# 02_BLBB_MCU.net
KiCad netlist of a schematic drawn in Altium Designer
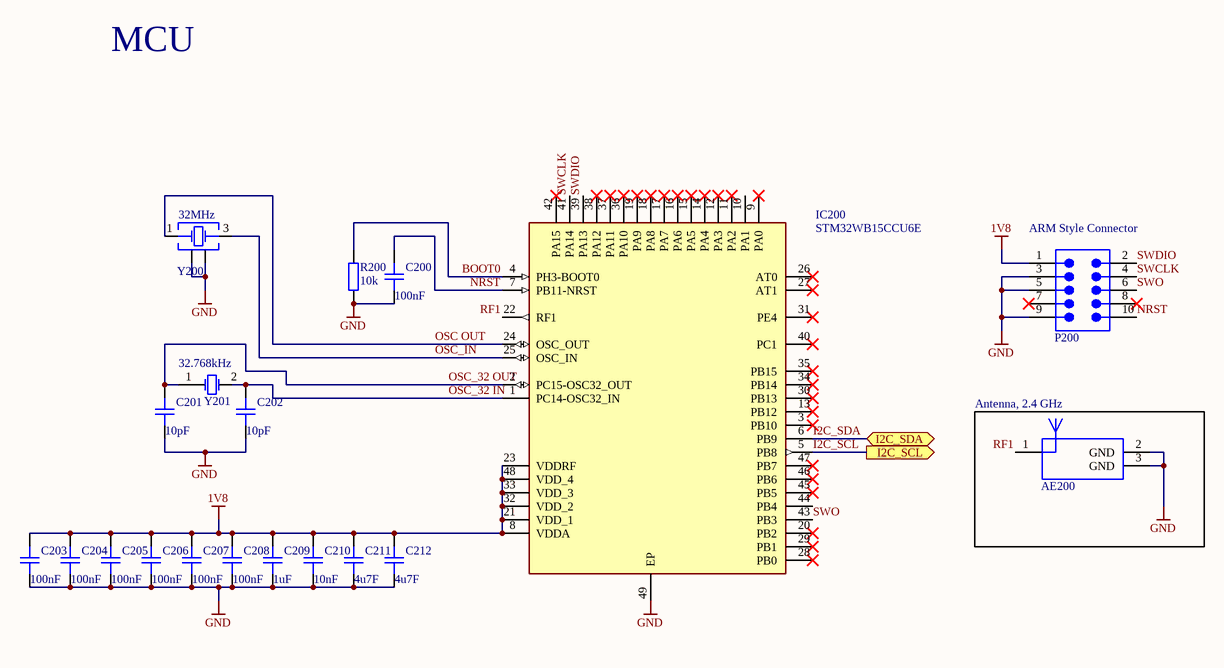
[diagram p0: 02_BLBB_MCU.SchDoc]

(export (version "E")
  (design (tool "Eeschema 10.0.6"))
  (components
    (comp (ref "AE200")
      (value "7488960245")
      (footprint "7488960245")
      (description "WE-MCA SMT Multilayer Chip Antenna, 1 Band, 2400-2500MHz, 50Ω")
      (fields (field (name "MANUFACTURER") "Wurth Elektronik"))
      (libsource (lib "WE-MCA") (part "7488960245"))
    )
    (comp (ref "C200")
      (value "100nF")
      (footprint "CAP_0603")
      (description "Capacitor SMD 0603 10V")
      (libsource (lib "Schematic-Lib-PhilsLab") (part "CAP_0603_10V"))
    )
    (comp (ref "C201")
      (value "10pF")
      (footprint "CAP_0603")
      (description "Capacitor SMD 0603 10V")
      (libsource (lib "Schematic-Lib-PhilsLab") (part "CAP_0603_10V"))
    )
    (comp (ref "C202")
      (value "10pF")
      (footprint "CAP_0603")
      (description "Capacitor SMD 0603 10V")
      (libsource (lib "Schematic-Lib-PhilsLab") (part "CAP_0603_10V"))
    )
    (comp (ref "C203")
      (value "100nF")
      (footprint "CAP_0603")
      (description "Capacitor SMD 0603 10V")
      (libsource (lib "Schematic-Lib-PhilsLab") (part "CAP_0603_10V"))
    )
    (comp (ref "C204")
      (value "100nF")
      (footprint "CAP_0603")
      (description "Capacitor SMD 0603 10V")
      (libsource (lib "Schematic-Lib-PhilsLab") (part "CAP_0603_10V"))
    )
    (comp (ref "C205")
      (value "100nF")
      (footprint "CAP_0603")
      (description "Capacitor SMD 0603 10V")
      (libsource (lib "Schematic-Lib-PhilsLab") (part "CAP_0603_10V"))
    )
    (comp (ref "C206")
      (value "100nF")
      (footprint "CAP_0603")
      (description "Capacitor SMD 0603 10V")
      (libsource (lib "Schematic-Lib-PhilsLab") (part "CAP_0603_10V"))
    )
    (comp (ref "C207")
      (value "100nF")
      (footprint "CAP_0603")
      (description "Capacitor SMD 0603 10V")
      (libsource (lib "Schematic-Lib-PhilsLab") (part "CAP_0603_10V"))
    )
    (comp (ref "C208")
      (value "100nF")
      (footprint "CAP_0603")
      (description "Capacitor SMD 0603 10V")
      (libsource (lib "Schematic-Lib-PhilsLab") (part "CAP_0603_10V"))
    )
    (comp (ref "C209")
      (value "1uF")
      (footprint "CAP_0603")
      (description "Capacitor SMD 0603 10V")
      (libsource (lib "Schematic-Lib-PhilsLab") (part "CAP_0603_10V"))
    )
    (comp (ref "C210")
      (value "10nF")
      (footprint "CAP_0603")
      (description "Capacitor SMD 0603 10V")
      (libsource (lib "Schematic-Lib-PhilsLab") (part "CAP_0603_10V"))
    )
    (comp (ref "C211")
      (value "4u7F")
      (footprint "CAP_0603")
      (description "Capacitor SMD 0603 10V")
      (libsource (lib "Schematic-Lib-PhilsLab") (part "CAP_0603_10V"))
    )
    (comp (ref "C212")
      (value "4u7F")
      (footprint "CAP_0603")
      (description "Capacitor SMD 0603 10V")
      (libsource (lib "Schematic-Lib-PhilsLab") (part "CAP_0603_10V"))
    )
    (comp (ref "IC200")
      (value "STM32WB15CCU6E")
      (footprint "SamacSys:QFN50P700X700X65-49N-D")
      (description "Integrated Circuit")
      (fields (field (name "MOUSER PART NUMBER") "511-STM32WB15CCU6E"))
      (libsource (lib "SamacSys") (part "STM32WB15CCU6E"))
    )
    (comp (ref "P200")
      (value "62701020621")
      (footprint "62701020621")
      (description "WR-BHD Male Box Header, SMT Straight, pitch 1.27mm, 10pins")
      (fields (field (name "MANUFACTURER") "Wurth Elektronik"))
      (libsource (lib "Altium_WR-BHD (rev22b)") (part "62701020621"))
    )
    (comp (ref "R200")
      (value "10k")
      (footprint "RES_0603")
      (description "Resistor SMD 0603")
      (libsource (lib "Schematic-Lib-PhilsLab") (part "RES_0603"))
    )
    (comp (ref "Y200")
      (value "32MHz")
      (footprint "WE-XTAL_CFPX-180")
      (description "WE-XTAL Quartz Crystal, SMT, CFPX-180, 32MHz, +/-30ppm")
      (fields
        (field (name "MANUFACTURER PART NUMBER") "830060258")
        (field (name "MANUFACTURER") "Wurth Elektronik")
      )
      (libsource (lib "WE-XTAL") (part "830060258"))
    )
    (comp (ref "Y201")
      (value "32.768kHz")
      (footprint "WE-XTAL_CFPX-217")
      (description "WE-XTAL Watch Crystal, SMT, CFPX-217, 32.768kHz, +/-20ppm")
      (fields
        (field (name "MANUFACTURER PART NUMBER") "830009709")
        (field (name "MANUFACTURER") "Wurth Elektronik")
      )
      (libsource (lib "WE-XTAL") (part "830009709"))
    )
  )
  (nets
    (net (code "1") (name "/BOOT0") (class "Default")
      (node (ref "IC200") (pin "4") (pinfunction "PH3-BOOT0_4") (pintype "input"))
      (node (ref "R200") (pin "2") (pinfunction "2_2") (pintype "passive"))
    )
    (net (code "2") (name "/I2C_SCL") (class "Default")
      (node (ref "IC200") (pin "5") (pinfunction "PB8_5") (pintype "output"))
    )
    (net (code "3") (name "/I2C_SDA") (class "Default")
      (node (ref "IC200") (pin "6") (pinfunction "PB9_6") (pintype "passive"))
    )
    (net (code "4") (name "/NRST") (class "Default")
      (node (ref "C200") (pin "2") (pinfunction "2_2") (pintype "passive"))
      (node (ref "IC200") (pin "7") (pinfunction "PB11-NRST_7") (pintype "input"))
      (node (ref "P200") (pin "10") (pinfunction "10_10") (pintype "passive"))
    )
    (net (code "5") (name "/OSC OUT") (class "Default")
      (node (ref "IC200") (pin "24") (pinfunction "OSC_OUT_24") (pintype "bidirectional"))
      (node (ref "Y200") (pin "1") (pinfunction "Crystal_1") (pintype "passive"))
    )
    (net (code "6") (name "/OSC_32 IN") (class "Default")
      (node (ref "C202") (pin "2") (pinfunction "2_2") (pintype "passive"))
      (node (ref "IC200") (pin "1") (pinfunction "PC14-OSC32_IN_1") (pintype "open_collector"))
      (node (ref "Y201") (pin "2") (pinfunction "OSC2_2") (pintype "passive"))
    )
    (net (code "7") (name "/OSC_32 OUT") (class "Default")
      (node (ref "C201") (pin "2") (pinfunction "2_2") (pintype "passive"))
      (node (ref "IC200") (pin "2") (pinfunction "PC15-OSC32_OUT_2") (pintype "bidirectional"))
      (node (ref "Y201") (pin "1") (pinfunction "OSC1_1") (pintype "passive"))
    )
    (net (code "8") (name "/OSC_IN") (class "Default")
      (node (ref "IC200") (pin "25") (pinfunction "OSC_IN_25") (pintype "bidirectional"))
      (node (ref "Y200") (pin "3") (pinfunction "Crystal_3") (pintype "passive"))
    )
    (net (code "9") (name "/RF1") (class "Default")
      (node (ref "AE200") (pin "1") (pinfunction "Feed_1") (pintype "passive"))
      (node (ref "IC200") (pin "22") (pinfunction "RF1_22") (pintype "output"))
    )
    (net (code "10") (name "/SWCLK") (class "Default")
      (node (ref "IC200") (pin "41") (pinfunction "PA14_41") (pintype "passive"))
      (node (ref "P200") (pin "4") (pinfunction "4_4") (pintype "passive"))
    )
    (net (code "11") (name "/SWDIO") (class "Default")
      (node (ref "IC200") (pin "39") (pinfunction "PA13_39") (pintype "passive"))
      (node (ref "P200") (pin "2") (pinfunction "2_2") (pintype "passive"))
    )
    (net (code "12") (name "/SWO") (class "Default")
      (node (ref "IC200") (pin "43") (pinfunction "PB3_43") (pintype "passive"))
      (node (ref "P200") (pin "6") (pinfunction "6_6") (pintype "passive"))
    )
    (net (code "13") (name "1V8") (class "Default")
      (node (ref "C203") (pin "2") (pinfunction "2_2") (pintype "passive"))
      (node (ref "C204") (pin "2") (pinfunction "2_2") (pintype "passive"))
      (node (ref "C205") (pin "2") (pinfunction "2_2") (pintype "passive"))
      (node (ref "C206") (pin "2") (pinfunction "2_2") (pintype "passive"))
      (node (ref "C207") (pin "2") (pinfunction "2_2") (pintype "passive"))
      (node (ref "C208") (pin "2") (pinfunction "2_2") (pintype "passive"))
      (node (ref "C209") (pin "2") (pinfunction "2_2") (pintype "passive"))
      (node (ref "C210") (pin "2") (pinfunction "2_2") (pintype "passive"))
      (node (ref "C211") (pin "2") (pinfunction "2_2") (pintype "passive"))
      (node (ref "C212") (pin "2") (pinfunction "2_2") (pintype "passive"))
      (node (ref "IC200") (pin "21") (pinfunction "VDD_1_21") (pintype "passive"))
      (node (ref "IC200") (pin "23") (pinfunction "VDDRF_23") (pintype "power_in"))
      (node (ref "IC200") (pin "32") (pinfunction "VDD_2_32") (pintype "power_in"))
      (node (ref "IC200") (pin "33") (pinfunction "VDD_3_33") (pintype "power_in"))
      (node (ref "IC200") (pin "48") (pinfunction "VDD_4_48") (pintype "power_in"))
      (node (ref "IC200") (pin "8") (pinfunction "VDDA_8") (pintype "power_in"))
      (node (ref "P200") (pin "1") (pinfunction "1_1") (pintype "passive"))
    )
    (net (code "14") (name "GND") (class "Default")
      (node (ref "AE200") (pin "2") (pinfunction "GND_2") (pintype "passive"))
      (node (ref "AE200") (pin "3") (pinfunction "GND_3") (pintype "passive"))
      (node (ref "C200") (pin "1") (pinfunction "1_1") (pintype "passive"))
      (node (ref "C201") (pin "1") (pinfunction "1_1") (pintype "passive"))
      (node (ref "C202") (pin "1") (pinfunction "1_1") (pintype "passive"))
      (node (ref "C203") (pin "1") (pinfunction "1_1") (pintype "passive"))
      (node (ref "C204") (pin "1") (pinfunction "1_1") (pintype "passive"))
      (node (ref "C205") (pin "1") (pinfunction "1_1") (pintype "passive"))
      (node (ref "C206") (pin "1") (pinfunction "1_1") (pintype "passive"))
      (node (ref "C207") (pin "1") (pinfunction "1_1") (pintype "passive"))
      (node (ref "C208") (pin "1") (pinfunction "1_1") (pintype "passive"))
      (node (ref "C209") (pin "1") (pinfunction "1_1") (pintype "passive"))
      (node (ref "C210") (pin "1") (pinfunction "1_1") (pintype "passive"))
      (node (ref "C211") (pin "1") (pinfunction "1_1") (pintype "passive"))
      (node (ref "C212") (pin "1") (pinfunction "1_1") (pintype "passive"))
      (node (ref "IC200") (pin "49") (pinfunction "EP_49") (pintype "power_in"))
      (node (ref "P200") (pin "3") (pinfunction "3_3") (pintype "passive"))
      (node (ref "P200") (pin "5") (pinfunction "5_5") (pintype "passive"))
      (node (ref "P200") (pin "9") (pinfunction "9_9") (pintype "passive"))
      (node (ref "R200") (pin "1") (pinfunction "1_1") (pintype "passive"))
      (node (ref "Y200") (pin "2") (pinfunction "GND&Lid_2") (pintype "passive"))
      (node (ref "Y200") (pin "4") (pinfunction "GND&Lid_4") (pintype "passive"))
    )
    (net (code "15") (name "unconnected-(IC200-AT0-Pad26)") (class "Default")
      (node (ref "IC200") (pin "26") (pinfunction "AT0_26") (pintype "passive+no_connect"))
    )
    (net (code "16") (name "unconnected-(IC200-AT1-Pad27)") (class "Default")
      (node (ref "IC200") (pin "27") (pinfunction "AT1_27") (pintype "passive+no_connect"))
    )
    (net (code "17") (name "unconnected-(IC200-PA0-Pad9)") (class "Default")
      (node (ref "IC200") (pin "9") (pinfunction "PA0_9") (pintype "passive+no_connect"))
    )
    (net (code "18") (name "unconnected-(IC200-PA1-Pad10)") (class "Default")
      (node (ref "IC200") (pin "10") (pinfunction "PA1_10") (pintype "passive"))
    )
    (net (code "19") (name "unconnected-(IC200-PA2-Pad11)") (class "Default")
      (node (ref "IC200") (pin "11") (pinfunction "PA2_11") (pintype "passive+no_connect"))
    )
    (net (code "20") (name "unconnected-(IC200-PA3-Pad12)") (class "Default")
      (node (ref "IC200") (pin "12") (pinfunction "PA3_12") (pintype "passive+no_connect"))
    )
    (net (code "21") (name "unconnected-(IC200-PA4-Pad14)") (class "Default")
      (node (ref "IC200") (pin "14") (pinfunction "PA4_14") (pintype "passive+no_connect"))
    )
    (net (code "22") (name "unconnected-(IC200-PA5-Pad15)") (class "Default")
      (node (ref "IC200") (pin "15") (pinfunction "PA5_15") (pintype "passive+no_connect"))
    )
    (net (code "23") (name "unconnected-(IC200-PA6-Pad16)") (class "Default")
      (node (ref "IC200") (pin "16") (pinfunction "PA6_16") (pintype "passive+no_connect"))
    )
    (net (code "24") (name "unconnected-(IC200-PA7-Pad17)") (class "Default")
      (node (ref "IC200") (pin "17") (pinfunction "PA7_17") (pintype "passive+no_connect"))
    )
    (net (code "25") (name "unconnected-(IC200-PA8-Pad18)") (class "Default")
      (node (ref "IC200") (pin "18") (pinfunction "PA8_18") (pintype "passive+no_connect"))
    )
    (net (code "26") (name "unconnected-(IC200-PA9-Pad19)") (class "Default")
      (node (ref "IC200") (pin "19") (pinfunction "PA9_19") (pintype "passive+no_connect"))
    )
    (net (code "27") (name "unconnected-(IC200-PA10-Pad36)") (class "Default")
      (node (ref "IC200") (pin "36") (pinfunction "PA10_36") (pintype "passive+no_connect"))
    )
    (net (code "28") (name "unconnected-(IC200-PA11-Pad37)") (class "Default")
      (node (ref "IC200") (pin "37") (pinfunction "PA11_37") (pintype "passive+no_connect"))
    )
    (net (code "29") (name "unconnected-(IC200-PA12-Pad38)") (class "Default")
      (node (ref "IC200") (pin "38") (pinfunction "PA12_38") (pintype "passive+no_connect"))
    )
    (net (code "30") (name "unconnected-(IC200-PA15-Pad42)") (class "Default")
      (node (ref "IC200") (pin "42") (pinfunction "PA15_42") (pintype "passive+no_connect"))
    )
    (net (code "31") (name "unconnected-(IC200-PB0-Pad28)") (class "Default")
      (node (ref "IC200") (pin "28") (pinfunction "PB0_28") (pintype "passive+no_connect"))
    )
    (net (code "32") (name "unconnected-(IC200-PB1-Pad29)") (class "Default")
      (node (ref "IC200") (pin "29") (pinfunction "PB1_29") (pintype "passive+no_connect"))
    )
    (net (code "33") (name "unconnected-(IC200-PB2-Pad20)") (class "Default")
      (node (ref "IC200") (pin "20") (pinfunction "PB2_20") (pintype "passive+no_connect"))
    )
    (net (code "34") (name "unconnected-(IC200-PB4-Pad44)") (class "Default")
      (node (ref "IC200") (pin "44") (pinfunction "PB4_44") (pintype "passive"))
    )
    (net (code "35") (name "unconnected-(IC200-PB5-Pad45)") (class "Default")
      (node (ref "IC200") (pin "45") (pinfunction "PB5_45") (pintype "passive+no_connect"))
    )
    (net (code "36") (name "unconnected-(IC200-PB6-Pad46)") (class "Default")
      (node (ref "IC200") (pin "46") (pinfunction "PB6_46") (pintype "passive+no_connect"))
    )
    (net (code "37") (name "unconnected-(IC200-PB7-Pad47)") (class "Default")
      (node (ref "IC200") (pin "47") (pinfunction "PB7_47") (pintype "passive+no_connect"))
    )
    (net (code "38") (name "unconnected-(IC200-PB10-Pad3)") (class "Default")
      (node (ref "IC200") (pin "3") (pinfunction "PB10_3") (pintype "passive+no_connect"))
    )
    (net (code "39") (name "unconnected-(IC200-PB12-Pad13)") (class "Default")
      (node (ref "IC200") (pin "13") (pinfunction "PB12_13") (pintype "passive+no_connect"))
    )
    (net (code "40") (name "unconnected-(IC200-PB13-Pad30)") (class "Default")
      (node (ref "IC200") (pin "30") (pinfunction "PB13_30") (pintype "passive+no_connect"))
    )
    (net (code "41") (name "unconnected-(IC200-PB14-Pad34)") (class "Default")
      (node (ref "IC200") (pin "34") (pinfunction "PB14_34") (pintype "passive+no_connect"))
    )
    (net (code "42") (name "unconnected-(IC200-PB15-Pad35)") (class "Default")
      (node (ref "IC200") (pin "35") (pinfunction "PB15_35") (pintype "passive+no_connect"))
    )
    (net (code "43") (name "unconnected-(IC200-PC1-Pad40)") (class "Default")
      (node (ref "IC200") (pin "40") (pinfunction "PC1_40") (pintype "passive+no_connect"))
    )
    (net (code "44") (name "unconnected-(IC200-PE4-Pad31)") (class "Default")
      (node (ref "IC200") (pin "31") (pinfunction "PE4_31") (pintype "passive+no_connect"))
    )
    (net (code "45") (name "unconnected-(P200-Pad7)") (class "Default")
      (node (ref "P200") (pin "7") (pinfunction "7_7") (pintype "passive+no_connect"))
    )
    (net (code "46") (name "unconnected-(P200-Pad8)") (class "Default")
      (node (ref "P200") (pin "8") (pinfunction "8_8") (pintype "passive+no_connect"))
    )
  )
)
